# System_Regulators.net
KiCad netlist of a schematic drawn in Altium Designer
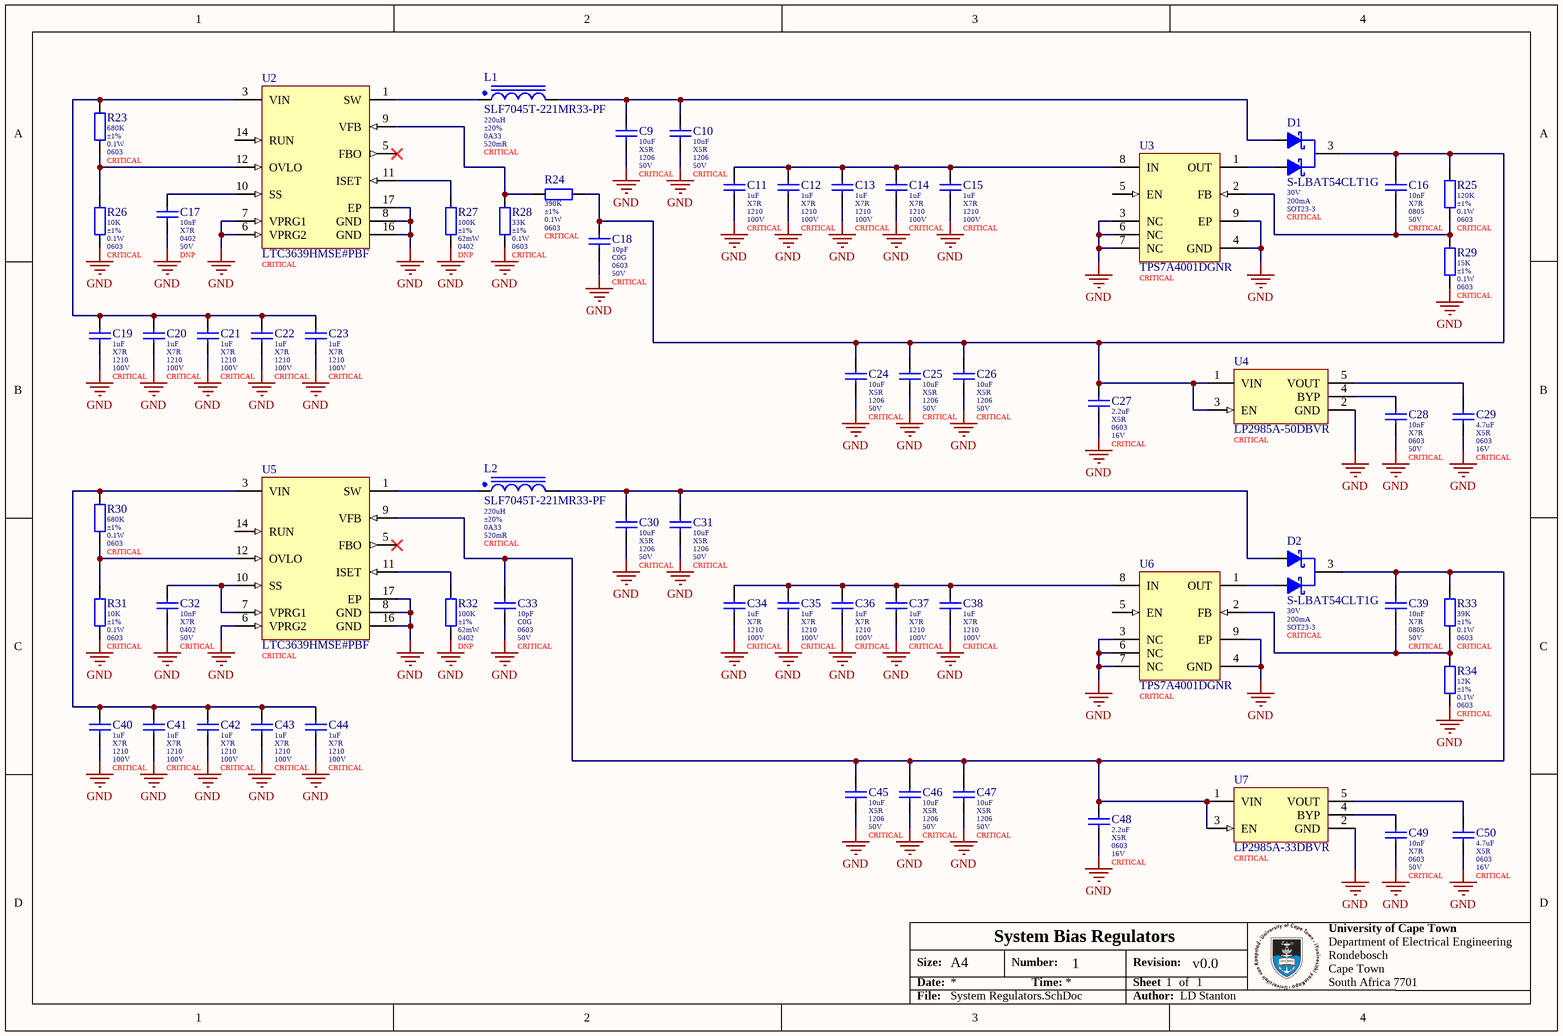
[diagram p0: System Regulators.SchDoc]

(export (version "E")
  (design (tool "Eeschema 10.0.6"))
  (components
    (comp (ref "C9")
      (value "10uF")
      (footprint "1206_160_H_N")
      (description "MLCC 10uF 1206 50V X5R ±10%")
      (fields
        (field (name "DIELECTRIC") "X5R")
        (field (name "PACKAGE") "1206")
        (field (name "VOLTAGE") "50V")
        (field (name "POPULATE") "CRITICAL")
        (field (name "LCSC PART NUMBER") "C13585")
        (field (name "MANUFACTURER") "Samsung")
      )
      (libsource (lib "University of Cape Town") (part "Symbol"))
    )
    (comp (ref "C10")
      (value "10uF")
      (footprint "1206_160_H_N")
      (description "MLCC 10uF 1206 50V X5R ±10%")
      (fields
        (field (name "DIELECTRIC") "X5R")
        (field (name "PACKAGE") "1206")
        (field (name "VOLTAGE") "50V")
        (field (name "POPULATE") "CRITICAL")
        (field (name "LCSC PART NUMBER") "C13585")
        (field (name "MANUFACTURER") "Samsung")
      )
      (libsource (lib "University of Cape Town") (part "Symbol"))
    )
    (comp (ref "C11")
      (value "1uF")
      (footprint "1210_250_J_N")
      (description "MLCC 1uF 1210 100V X7R ±10%")
      (fields
        (field (name "DIELECTRIC") "X7R")
        (field (name "PACKAGE") "1210")
        (field (name "VOLTAGE") "100V")
        (field (name "POPULATE") "CRITICAL")
        (field (name "LCSC PART NUMBER") "C444847")
        (field (name "TOLERANCE") "±10%")
      )
      (libsource (lib "University of Cape Town") (part "Symbol"))
    )
    (comp (ref "C12")
      (value "1uF")
      (footprint "1210_250_J_N")
      (description "MLCC 1uF 1210 100V X7R ±10%")
      (fields
        (field (name "DIELECTRIC") "X7R")
        (field (name "PACKAGE") "1210")
        (field (name "VOLTAGE") "100V")
        (field (name "POPULATE") "CRITICAL")
        (field (name "LCSC PART NUMBER") "C444847")
        (field (name "TOLERANCE") "±10%")
      )
      (libsource (lib "University of Cape Town") (part "Symbol"))
    )
    (comp (ref "C13")
      (value "1uF")
      (footprint "1210_250_J_N")
      (description "MLCC 1uF 1210 100V X7R ±10%")
      (fields
        (field (name "DIELECTRIC") "X7R")
        (field (name "PACKAGE") "1210")
        (field (name "VOLTAGE") "100V")
        (field (name "POPULATE") "CRITICAL")
        (field (name "LCSC PART NUMBER") "C444847")
        (field (name "TOLERANCE") "±10%")
      )
      (libsource (lib "University of Cape Town") (part "Symbol"))
    )
    (comp (ref "C14")
      (value "1uF")
      (footprint "1210_250_J_N")
      (description "MLCC 1uF 1210 100V X7R ±10%")
      (fields
        (field (name "DIELECTRIC") "X7R")
        (field (name "PACKAGE") "1210")
        (field (name "VOLTAGE") "100V")
        (field (name "POPULATE") "CRITICAL")
        (field (name "LCSC PART NUMBER") "C444847")
        (field (name "TOLERANCE") "±10%")
      )
      (libsource (lib "University of Cape Town") (part "Symbol"))
    )
    (comp (ref "C15")
      (value "1uF")
      (footprint "1210_250_J_N")
      (description "MLCC 1uF 1210 100V X7R ±10%")
      (fields
        (field (name "DIELECTRIC") "X7R")
        (field (name "PACKAGE") "1210")
        (field (name "VOLTAGE") "100V")
        (field (name "POPULATE") "CRITICAL")
        (field (name "LCSC PART NUMBER") "C444847")
        (field (name "TOLERANCE") "±10%")
      )
      (libsource (lib "University of Cape Town") (part "Symbol"))
    )
    (comp (ref "C16")
      (value "10nF")
      (footprint "0605_065_A_N")
      (description "MLCC 10nF 0805 50V X7R ±10%")
      (fields
        (field (name "DIELECTRIC") "X7R")
        (field (name "PACKAGE") "0805")
        (field (name "VOLTAGE") "50V")
        (field (name "POPULATE") "CRITICAL")
        (field (name "LCSC PART NUMBER") "C1710")
        (field (name "MANUFACTURER") "Samsung")
      )
      (libsource (lib "University of Cape Town") (part "Symbol"))
    )
    (comp (ref "C17")
      (value "10nF")
      (footprint "0402_050_5_N")
      (description "MLCC 10nF 0402 50V X7R ±10%")
      (fields
        (field (name "DIELECTRIC") "X7R")
        (field (name "PACKAGE") "0402")
        (field (name "VOLTAGE") "50V")
        (field (name "POPULATE") "DNP")
        (field (name "TOLERANCE") "±10%")
        (field (name "LCSC PART NUMBER") "C15195")
      )
      (libsource (lib "University of Cape Town") (part "Symbol"))
    )
    (comp (ref "C18")
      (value "10pF")
      (footprint "0603_080_8_N")
      (description "MLCC 10pF 0603 C0G ±0.1pF")
      (fields
        (field (name "DIELECTRIC") "C0G")
        (field (name "PACKAGE") "0603")
        (field (name "VOLTAGE") "50V")
        (field (name "POPULATE") "CRITICAL")
        (field (name "LCSC PART NUMBER") "C1634")
        (field (name "MANUFACTURER") "Samsung")
      )
      (libsource (lib "University of Cape Town") (part "Symbol"))
    )
    (comp (ref "C19")
      (value "1uF")
      (footprint "1210_250_J_N")
      (description "MLCC 1uF 1210 100V X7R ±10%")
      (fields
        (field (name "DIELECTRIC") "X7R")
        (field (name "PACKAGE") "1210")
        (field (name "VOLTAGE") "100V")
        (field (name "POPULATE") "CRITICAL")
        (field (name "LCSC PART NUMBER") "C444847")
        (field (name "TOLERANCE") "±10%")
      )
      (libsource (lib "University of Cape Town") (part "Symbol"))
    )
    (comp (ref "C20")
      (value "1uF")
      (footprint "1210_250_J_N")
      (description "MLCC 1uF 1210 100V X7R ±10%")
      (fields
        (field (name "DIELECTRIC") "X7R")
        (field (name "PACKAGE") "1210")
        (field (name "VOLTAGE") "100V")
        (field (name "POPULATE") "CRITICAL")
        (field (name "LCSC PART NUMBER") "C444847")
        (field (name "TOLERANCE") "±10%")
      )
      (libsource (lib "University of Cape Town") (part "Symbol"))
    )
    (comp (ref "C21")
      (value "1uF")
      (footprint "1210_250_J_N")
      (description "MLCC 1uF 1210 100V X7R ±10%")
      (fields
        (field (name "DIELECTRIC") "X7R")
        (field (name "PACKAGE") "1210")
        (field (name "VOLTAGE") "100V")
        (field (name "POPULATE") "CRITICAL")
        (field (name "LCSC PART NUMBER") "C444847")
        (field (name "TOLERANCE") "±10%")
      )
      (libsource (lib "University of Cape Town") (part "Symbol"))
    )
    (comp (ref "C22")
      (value "1uF")
      (footprint "1210_250_J_N")
      (description "MLCC 1uF 1210 100V X7R ±10%")
      (fields
        (field (name "DIELECTRIC") "X7R")
        (field (name "PACKAGE") "1210")
        (field (name "VOLTAGE") "100V")
        (field (name "POPULATE") "CRITICAL")
        (field (name "LCSC PART NUMBER") "C444847")
        (field (name "TOLERANCE") "±10%")
      )
      (libsource (lib "University of Cape Town") (part "Symbol"))
    )
    (comp (ref "C23")
      (value "1uF")
      (footprint "1210_250_J_N")
      (description "MLCC 1uF 1210 100V X7R ±10%")
      (fields
        (field (name "DIELECTRIC") "X7R")
        (field (name "PACKAGE") "1210")
        (field (name "VOLTAGE") "100V")
        (field (name "POPULATE") "CRITICAL")
        (field (name "LCSC PART NUMBER") "C444847")
        (field (name "TOLERANCE") "±10%")
      )
      (libsource (lib "University of Cape Town") (part "Symbol"))
    )
    (comp (ref "C24")
      (value "10uF")
      (footprint "1206_160_H_N")
      (description "MLCC 10uF 1206 50V X5R ±10%")
      (fields
        (field (name "DIELECTRIC") "X5R")
        (field (name "PACKAGE") "1206")
        (field (name "VOLTAGE") "50V")
        (field (name "POPULATE") "CRITICAL")
        (field (name "LCSC PART NUMBER") "C13585")
        (field (name "MANUFACTURER") "Samsung")
      )
      (libsource (lib "University of Cape Town") (part "Symbol"))
    )
    (comp (ref "C25")
      (value "10uF")
      (footprint "1206_160_H_N")
      (description "MLCC 10uF 1206 50V X5R ±10%")
      (fields
        (field (name "DIELECTRIC") "X5R")
        (field (name "PACKAGE") "1206")
        (field (name "VOLTAGE") "50V")
        (field (name "POPULATE") "CRITICAL")
        (field (name "LCSC PART NUMBER") "C13585")
        (field (name "MANUFACTURER") "Samsung")
      )
      (libsource (lib "University of Cape Town") (part "Symbol"))
    )
    (comp (ref "C26")
      (value "10uF")
      (footprint "1206_160_H_N")
      (description "MLCC 10uF 1206 50V X5R ±10%")
      (fields
        (field (name "DIELECTRIC") "X5R")
        (field (name "PACKAGE") "1206")
        (field (name "VOLTAGE") "50V")
        (field (name "POPULATE") "CRITICAL")
        (field (name "LCSC PART NUMBER") "C13585")
        (field (name "MANUFACTURER") "Samsung")
      )
      (libsource (lib "University of Cape Town") (part "Symbol"))
    )
    (comp (ref "C27")
      (value "2.2uF")
      (footprint "0603_080_8_N")
      (description "MLCC 2.2uF 0603 16V X5R ±10%")
      (fields
        (field (name "DIELECTRIC") "X5R")
        (field (name "PACKAGE") "0603")
        (field (name "VOLTAGE") "16V")
        (field (name "POPULATE") "CRITICAL")
        (field (name "TOLERANCE") "±10%")
        (field (name "LCSC PART NUMBER") "C23630")
      )
      (libsource (lib "University of Cape Town") (part "Symbol"))
    )
    (comp (ref "C28")
      (value "10nF")
      (footprint "0603_080")
      (description "MLCC 10nF 0603 50V X7R ±10%")
      (fields
        (field (name "DIELECTRIC") "X7R")
        (field (name "PACKAGE") "0603")
        (field (name "VOLTAGE") "50V")
        (field (name "POPULATE") "CRITICAL")
        (field (name "LCSC PART NUMBER") "C57112")
        (field (name "MANUFACTURER") "Guandong")
      )
      (libsource (lib "University of Cape Town") (part "Symbol"))
    )
    (comp (ref "C29")
      (value "4.7uF")
      (footprint "0603_080_8_N")
      (description "MLCC 4.7uF 0603 16V X5R ±10%")
      (fields
        (field (name "DIELECTRIC") "X5R")
        (field (name "PACKAGE") "0603")
        (field (name "VOLTAGE") "16V")
        (field (name "POPULATE") "CRITICAL")
        (field (name "LCSC PART NUMBER") "C19666")
        (field (name "TOLERANCE") "±10%")
      )
      (libsource (lib "University of Cape Town") (part "Symbol"))
    )
    (comp (ref "C30")
      (value "10uF")
      (footprint "1206_160_H_N")
      (description "MLCC 10uF 1206 50V X5R ±10%")
      (fields
        (field (name "DIELECTRIC") "X5R")
        (field (name "PACKAGE") "1206")
        (field (name "VOLTAGE") "50V")
        (field (name "POPULATE") "CRITICAL")
        (field (name "LCSC PART NUMBER") "C13585")
        (field (name "MANUFACTURER") "Samsung")
      )
      (libsource (lib "University of Cape Town") (part "Symbol"))
    )
    (comp (ref "C31")
      (value "10uF")
      (footprint "1206_160_H_N")
      (description "MLCC 10uF 1206 50V X5R ±10%")
      (fields
        (field (name "DIELECTRIC") "X5R")
        (field (name "PACKAGE") "1206")
        (field (name "VOLTAGE") "50V")
        (field (name "POPULATE") "CRITICAL")
        (field (name "LCSC PART NUMBER") "C13585")
        (field (name "MANUFACTURER") "Samsung")
      )
      (libsource (lib "University of Cape Town") (part "Symbol"))
    )
    (comp (ref "C32")
      (value "10nF")
      (footprint "0402_050_5_N")
      (description "MLCC 10nF 0402 50V X7R ±10%")
      (fields
        (field (name "DIELECTRIC") "X7R")
        (field (name "PACKAGE") "0402")
        (field (name "VOLTAGE") "50V")
        (field (name "POPULATE") "CRITICAL")
        (field (name "TOLERANCE") "±10%")
        (field (name "LCSC PART NUMBER") "C15195")
      )
      (libsource (lib "University of Cape Town") (part "Symbol"))
    )
    (comp (ref "C33")
      (value "10pF")
      (footprint "0603_080_8_N")
      (description "MLCC 10pF 0603 C0G ±0.1pF")
      (fields
        (field (name "DIELECTRIC") "C0G")
        (field (name "PACKAGE") "0603")
        (field (name "VOLTAGE") "50V")
        (field (name "POPULATE") "CRITICAL")
        (field (name "LCSC PART NUMBER") "C1634")
        (field (name "MANUFACTURER") "Samsung")
      )
      (libsource (lib "University of Cape Town") (part "Symbol"))
    )
    (comp (ref "C34")
      (value "1uF")
      (footprint "1210_250_J_N")
      (description "MLCC 1uF 1210 100V X7R ±10%")
      (fields
        (field (name "DIELECTRIC") "X7R")
        (field (name "PACKAGE") "1210")
        (field (name "VOLTAGE") "100V")
        (field (name "POPULATE") "CRITICAL")
        (field (name "LCSC PART NUMBER") "C444847")
        (field (name "TOLERANCE") "±10%")
      )
      (libsource (lib "University of Cape Town") (part "Symbol"))
    )
    (comp (ref "C35")
      (value "1uF")
      (footprint "1210_250_J_N")
      (description "MLCC 1uF 1210 100V X7R ±10%")
      (fields
        (field (name "DIELECTRIC") "X7R")
        (field (name "PACKAGE") "1210")
        (field (name "VOLTAGE") "100V")
        (field (name "POPULATE") "CRITICAL")
        (field (name "LCSC PART NUMBER") "C444847")
        (field (name "TOLERANCE") "±10%")
      )
      (libsource (lib "University of Cape Town") (part "Symbol"))
    )
    (comp (ref "C36")
      (value "1uF")
      (footprint "1210_250_J_N")
      (description "MLCC 1uF 1210 100V X7R ±10%")
      (fields
        (field (name "DIELECTRIC") "X7R")
        (field (name "PACKAGE") "1210")
        (field (name "VOLTAGE") "100V")
        (field (name "POPULATE") "CRITICAL")
        (field (name "LCSC PART NUMBER") "C444847")
        (field (name "TOLERANCE") "±10%")
      )
      (libsource (lib "University of Cape Town") (part "Symbol"))
    )
    (comp (ref "C37")
      (value "1uF")
      (footprint "1210_250_J_N")
      (description "MLCC 1uF 1210 100V X7R ±10%")
      (fields
        (field (name "DIELECTRIC") "X7R")
        (field (name "PACKAGE") "1210")
        (field (name "VOLTAGE") "100V")
        (field (name "POPULATE") "CRITICAL")
        (field (name "LCSC PART NUMBER") "C444847")
        (field (name "TOLERANCE") "±10%")
      )
      (libsource (lib "University of Cape Town") (part "Symbol"))
    )
    (comp (ref "C38")
      (value "1uF")
      (footprint "1210_250_J_N")
      (description "MLCC 1uF 1210 100V X7R ±10%")
      (fields
        (field (name "DIELECTRIC") "X7R")
        (field (name "PACKAGE") "1210")
        (field (name "VOLTAGE") "100V")
        (field (name "POPULATE") "CRITICAL")
        (field (name "LCSC PART NUMBER") "C444847")
        (field (name "TOLERANCE") "±10%")
      )
      (libsource (lib "University of Cape Town") (part "Symbol"))
    )
    (comp (ref "C39")
      (value "10nF")
      (footprint "0605_065_A_N")
      (description "MLCC 10nF 0805 50V X7R ±10%")
      (fields
        (field (name "DIELECTRIC") "X7R")
        (field (name "PACKAGE") "0805")
        (field (name "VOLTAGE") "50V")
        (field (name "POPULATE") "CRITICAL")
        (field (name "LCSC PART NUMBER") "C1710")
        (field (name "MANUFACTURER") "Samsung")
      )
      (libsource (lib "University of Cape Town") (part "Symbol"))
    )
    (comp (ref "C40")
      (value "1uF")
      (footprint "1210_250_J_N")
      (description "MLCC 1uF 1210 100V X7R ±10%")
      (fields
        (field (name "DIELECTRIC") "X7R")
        (field (name "PACKAGE") "1210")
        (field (name "VOLTAGE") "100V")
        (field (name "POPULATE") "CRITICAL")
        (field (name "LCSC PART NUMBER") "C444847")
        (field (name "TOLERANCE") "±10%")
      )
      (libsource (lib "University of Cape Town") (part "Symbol"))
    )
    (comp (ref "C41")
      (value "1uF")
      (footprint "1210_250_J_N")
      (description "MLCC 1uF 1210 100V X7R ±10%")
      (fields
        (field (name "DIELECTRIC") "X7R")
        (field (name "PACKAGE") "1210")
        (field (name "VOLTAGE") "100V")
        (field (name "POPULATE") "CRITICAL")
        (field (name "LCSC PART NUMBER") "C444847")
        (field (name "TOLERANCE") "±10%")
      )
      (libsource (lib "University of Cape Town") (part "Symbol"))
    )
    (comp (ref "C42")
      (value "1uF")
      (footprint "1210_250_J_N")
      (description "MLCC 1uF 1210 100V X7R ±10%")
      (fields
        (field (name "DIELECTRIC") "X7R")
        (field (name "PACKAGE") "1210")
        (field (name "VOLTAGE") "100V")
        (field (name "POPULATE") "CRITICAL")
        (field (name "LCSC PART NUMBER") "C444847")
        (field (name "TOLERANCE") "±10%")
      )
      (libsource (lib "University of Cape Town") (part "Symbol"))
    )
    (comp (ref "C43")
      (value "1uF")
      (footprint "1210_250_J_N")
      (description "MLCC 1uF 1210 100V X7R ±10%")
      (fields
        (field (name "DIELECTRIC") "X7R")
        (field (name "PACKAGE") "1210")
        (field (name "VOLTAGE") "100V")
        (field (name "POPULATE") "CRITICAL")
        (field (name "LCSC PART NUMBER") "C444847")
        (field (name "TOLERANCE") "±10%")
      )
      (libsource (lib "University of Cape Town") (part "Symbol"))
    )
    (comp (ref "C44")
      (value "1uF")
      (footprint "1210_250_J_N")
      (description "MLCC 1uF 1210 100V X7R ±10%")
      (fields
        (field (name "DIELECTRIC") "X7R")
        (field (name "PACKAGE") "1210")
        (field (name "VOLTAGE") "100V")
        (field (name "POPULATE") "CRITICAL")
        (field (name "LCSC PART NUMBER") "C444847")
        (field (name "TOLERANCE") "±10%")
      )
      (libsource (lib "University of Cape Town") (part "Symbol"))
    )
    (comp (ref "C45")
      (value "10uF")
      (footprint "1206_160_H_N")
      (description "MLCC 10uF 1206 50V X5R ±10%")
      (fields
        (field (name "DIELECTRIC") "X5R")
        (field (name "PACKAGE") "1206")
        (field (name "VOLTAGE") "50V")
        (field (name "POPULATE") "CRITICAL")
        (field (name "LCSC PART NUMBER") "C13585")
        (field (name "MANUFACTURER") "Samsung")
      )
      (libsource (lib "University of Cape Town") (part "Symbol"))
    )
    (comp (ref "C46")
      (value "10uF")
      (footprint "1206_160_H_N")
      (description "MLCC 10uF 1206 50V X5R ±10%")
      (fields
        (field (name "DIELECTRIC") "X5R")
        (field (name "PACKAGE") "1206")
        (field (name "VOLTAGE") "50V")
        (field (name "POPULATE") "CRITICAL")
        (field (name "LCSC PART NUMBER") "C13585")
        (field (name "MANUFACTURER") "Samsung")
      )
      (libsource (lib "University of Cape Town") (part "Symbol"))
    )
    (comp (ref "C47")
      (value "10uF")
      (footprint "1206_160_H_N")
      (description "MLCC 10uF 1206 50V X5R ±10%")
      (fields
        (field (name "DIELECTRIC") "X5R")
        (field (name "PACKAGE") "1206")
        (field (name "VOLTAGE") "50V")
        (field (name "POPULATE") "CRITICAL")
        (field (name "LCSC PART NUMBER") "C13585")
        (field (name "MANUFACTURER") "Samsung")
      )
      (libsource (lib "University of Cape Town") (part "Symbol"))
    )
    (comp (ref "C48")
      (value "2.2uF")
      (footprint "0603_080_8_N")
      (description "MLCC 2.2uF 0603 16V X5R ±10%")
      (fields
        (field (name "DIELECTRIC") "X5R")
        (field (name "PACKAGE") "0603")
        (field (name "VOLTAGE") "16V")
        (field (name "POPULATE") "CRITICAL")
        (field (name "TOLERANCE") "±10%")
        (field (name "LCSC PART NUMBER") "C23630")
      )
      (libsource (lib "University of Cape Town") (part "Symbol"))
    )
    (comp (ref "C49")
      (value "10nF")
      (footprint "0603_080")
      (description "MLCC 10nF 0603 50V X7R ±10%")
      (fields
        (field (name "DIELECTRIC") "X7R")
        (field (name "PACKAGE") "0603")
        (field (name "VOLTAGE") "50V")
        (field (name "POPULATE") "CRITICAL")
        (field (name "LCSC PART NUMBER") "C57112")
        (field (name "MANUFACTURER") "Guandong")
      )
      (libsource (lib "University of Cape Town") (part "Symbol"))
    )
    (comp (ref "C50")
      (value "4.7uF")
      (footprint "0603_080_8_N")
      (description "MLCC 4.7uF 0603 16V X5R ±10%")
      (fields
        (field (name "DIELECTRIC") "X5R")
        (field (name "PACKAGE") "0603")
        (field (name "VOLTAGE") "16V")
        (field (name "POPULATE") "CRITICAL")
        (field (name "LCSC PART NUMBER") "C19666")
        (field (name "TOLERANCE") "±10%")
      )
      (libsource (lib "University of Cape Town") (part "Symbol"))
    )
    (comp (ref "D1")
      (value "S-LBAT54CLT1G")
      (footprint "SOT-23-3 (LBAT54C) B")
      (description "Schottky Barrier Diode Common Cathode 30V 200mA")
      (fields
        (field (name "REVERSE VOLTAGE") "30V")
        (field (name "FORWARD CURRENT") "200mA")
        (field (name "PACKAGE") "SOT23-3")
        (field (name "PLACEMENT") "CRITICAL")
        (field (name "MANUFACTURER") "LRC")
        (field (name "LCSC PART NUMBER") "C559091")
      )
      (libsource (lib "University of Cape Town") (part "BAT54"))
    )
    (comp (ref "D2")
      (value "S-LBAT54CLT1G")
      (footprint "SOT-23-3 (LBAT54C) B")
      (description "Schottky Barrier Diode Common Cathode 30V 200mA")
      (fields
        (field (name "REVERSE VOLTAGE") "30V")
        (field (name "FORWARD CURRENT") "200mA")
        (field (name "PACKAGE") "SOT23-3")
        (field (name "PLACEMENT") "CRITICAL")
        (field (name "MANUFACTURER") "LRC")
        (field (name "LCSC PART NUMBER") "C559091")
      )
      (libsource (lib "University of Cape Town") (part "BAT54"))
    )
    (comp (ref "L1")
      (value "SLF7045T-221MR33-PF")
      (footprint "SLF7045 B")
      (description "Inductor 220uH ±20% 0A65 470mR Wirewound Shielded")
      (fields
        (field (name "ALTIUM_VALUE") "220uH")
        (field (name "TOLERANCE") "±20%")
        (field (name "RATED CURRENT") "0A33")
        (field (name "DC RESISTANCE") "520mR")
        (field (name "POPULATE") "CRITICAL")
        (field (name "MANUFACTURER") "TDK")
        (field (name "LCSC PART NUMBER") "C24679")
      )
      (libsource (lib "University of Cape Town") (part "Inductor Core Polarised"))
    )
    (comp (ref "L2")
      (value "SLF7045T-221MR33-PF")
      (footprint "SLF7045 B")
      (description "Inductor 220uH ±20% 0A65 470mR Wirewound Shielded")
      (fields
        (field (name "ALTIUM_VALUE") "220uH")
        (field (name "TOLERANCE") "±20%")
        (field (name "RATED CURRENT") "0A33")
        (field (name "DC RESISTANCE") "520mR")
        (field (name "POPULATE") "CRITICAL")
        (field (name "MANUFACTURER") "TDK")
        (field (name "LCSC PART NUMBER") "C24679")
      )
      (libsource (lib "University of Cape Town") (part "Inductor Core Polarised"))
    )
    (comp (ref "R23")
      (value "680K")
      (footprint "0603")
      (description "Resistor 680K 0603 ±1% Thick Film Uniroyal")
      (fields
        (field (name "TOLERANCE") "±1%")
        (field (name "POWER") "0.1W")
        (field (name "PACKAGE") "0603")
        (field (name "POPULATE") "CRITICAL")
        (field (name "LCSC PART NUMBER") "C25822")
        (field (name "MANUFACTURER") "Uniroyal")
      )
      (libsource (lib "University of Cape Town") (part "Chip Resistor"))
    )
    (comp (ref "R24")
      (value "390K")
      (footprint "0603")
      (description "Resistor 390K 0603 ±1%Thick Film Uniroyal Elec")
      (fields
        (field (name "TOLERANCE") "±1%")
        (field (name "POWER") "0.1W")
        (field (name "PACKAGE") "0603")
        (field (name "POPULATE") "CRITICAL")
        (field (name "LCSC PART NUMBER") "C23150")
        (field (name "Comment") "0603WAF3903T5E")
      )
      (libsource (lib "University of Cape Town") (part "Chip Resistor"))
    )
    (comp (ref "R25")
      (value "120K")
      (footprint "0603")
      (description "Resistor 120K 0603 ±1% Thick Film Uniroyal")
      (fields
        (field (name "TOLERANCE") "±1%")
        (field (name "POWER") "0.1W")
        (field (name "PACKAGE") "0603")
        (field (name "POPULATE") "CRITICAL")
        (field (name "MANUFACTURER") "Uniroyal")
        (field (name "LCSC PART NUMBER") "C25808")
      )
      (libsource (lib "University of Cape Town") (part "Chip Resistor"))
    )
    (comp (ref "R26")
      (value "10K")
      (footprint "0603")
      (description "Resistor 10K 0603 ±1% Thick Film Uniroyal")
      (fields
        (field (name "TOLERANCE") "±1%")
        (field (name "POWER") "0.1W")
        (field (name "PACKAGE") "0603")
        (field (name "POPULATE") "CRITICAL")
        (field (name "MANUFACTURER") "Uniroyal")
        (field (name "LCSC PART NUMBER") "C25804")
      )
      (libsource (lib "University of Cape Town") (part "Chip Resistor"))
    )
    (comp (ref "R27")
      (value "100K")
      (footprint "0402")
      (description "Resistor 100K 0402 ±1% Thick Film Uniroyal")
      (fields
        (field (name "TOLERANCE") "±1%")
        (field (name "POWER") "62mW")
        (field (name "PACKAGE") "0402")
        (field (name "POPULATE") "DNP")
        (field (name "LCSC PART NUMBER") "C25741")
        (field (name "MANUFACTURER") "Uniroyal")
      )
      (libsource (lib "University of Cape Town") (part "Chip Resistor"))
    )
    (comp (ref "R28")
      (value "33K")
      (footprint "0603")
      (description "Resistor 33K 0603 ±1% Thick Film Uniroyal")
      (fields
        (field (name "TOLERANCE") "±1%")
        (field (name "POWER") "0.1W")
        (field (name "PACKAGE") "0603")
        (field (name "POPULATE") "CRITICAL")
        (field (name "LCSC PART NUMBER") "C4216")
        (field (name "MANUFACTURER") "Uniroyal")
      )
      (libsource (lib "University of Cape Town") (part "Chip Resistor"))
    )
    (comp (ref "R29")
      (value "15K")
      (footprint "0603")
      (description "Resistor 15K 0603 ±1% Thick Film Uniroyal")
      (fields
        (field (name "TOLERANCE") "±1%")
        (field (name "POWER") "0.1W")
        (field (name "PACKAGE") "0603")
        (field (name "POPULATE") "CRITICAL")
        (field (name "MANUFACTURER") "Uniroyal")
        (field (name "LCSC PART NUMBER") "C22809")
      )
      (libsource (lib "University of Cape Town") (part "Chip Resistor"))
    )
    (comp (ref "R30")
      (value "680K")
      (footprint "0603")
      (description "Resistor 680K 0603 ±1% Thick Film Uniroyal")
      (fields
        (field (name "TOLERANCE") "±1%")
        (field (name "POWER") "0.1W")
        (field (name "PACKAGE") "0603")
        (field (name "POPULATE") "CRITICAL")
        (field (name "LCSC PART NUMBER") "C25822")
        (field (name "MANUFACTURER") "Uniroyal")
      )
      (libsource (lib "University of Cape Town") (part "Chip Resistor"))
    )
    (comp (ref "R31")
      (value "10K")
      (footprint "0603")
      (description "Resistor 10K 0603 ±1% Thick Film Uniroyal")
      (fields
        (field (name "TOLERANCE") "±1%")
        (field (name "POWER") "0.1W")
        (field (name "PACKAGE") "0603")
        (field (name "POPULATE") "CRITICAL")
        (field (name "MANUFACTURER") "Uniroyal")
        (field (name "LCSC PART NUMBER") "C25804")
      )
      (libsource (lib "University of Cape Town") (part "Chip Resistor"))
    )
    (comp (ref "R32")
      (value "100K")
      (footprint "0402")
      (description "Resistor 100K 0402 ±1% Thick Film Uniroyal")
      (fields
        (field (name "TOLERANCE") "±1%")
        (field (name "POWER") "62mW")
        (field (name "PACKAGE") "0402")
        (field (name "POPULATE") "DNP")
        (field (name "LCSC PART NUMBER") "C25741")
        (field (name "MANUFACTURER") "Uniroyal")
      )
      (libsource (lib "University of Cape Town") (part "Chip Resistor"))
    )
    (comp (ref "R33")
      (value "39K")
      (footprint "0603")
      (description "Resistor 39K 0603 ±1% Thick Film Uniroyal")
      (fields
        (field (name "TOLERANCE") "±1%")
        (field (name "POWER") "0.1W")
        (field (name "PACKAGE") "0603")
        (field (name "POPULATE") "CRITICAL")
        (field (name "MANUFACTURER") "Uniroyal")
        (field (name "Comment") "0603WAF3902T5E")
      )
      (libsource (lib "University of Cape Town") (part "Chip Resistor"))
    )
    (comp (ref "R34")
      (value "12K")
      (footprint "0603")
      (description "Resistor 12K 0603 ±1% Thick Film Uniroyal")
      (fields
        (field (name "TOLERANCE") "±1%")
        (field (name "POWER") "0.1W")
        (field (name "PACKAGE") "0603")
        (field (name "POPULATE") "CRITICAL")
        (field (name "MANUFACTURER") "Uniroyal")
        (field (name "LCSC PART NUMBER") "C22790")
      )
      (libsource (lib "University of Cape Town") (part "Chip Resistor"))
    )
    (comp (ref "U2")
      (value "LTC3639HMSE#PBF")
      (footprint "LT-MSE-16-V(12)4PR-EDP_N")
      (description "DC-DC Conv 4V to 150V Synchronous Step Down Single-Out 0.8V to 150V 0.1A Automotive 12-Pin MSOP EP")
      (fields (field (name "PLACEMENT") "CRITICAL") (field (name "LCSC PART NUMBER") "C117279"))
      (libsource (lib "University of Cape Town") (part "LT-LTC3639-MSE-16"))
    )
    (comp (ref "U3")
      (value "TPS7A4001DGNR")
      (footprint "DGN0008B_N")
      (description "Adjustable LDO Voltage Regulator, 7 V to 100 V, 780 mV Drop, 1.161 V to 90 V / 50 mA out, MSOP-8")
      (fields
        (field (name "PLACEMENT") "CRITICAL")
        (field (name "LCSC PART NUMBER") "C55006")
        (field (name "POWER") "1.83W")
      )
      (libsource (lib "University of Cape Town") (part "TPS7A4001DGNR"))
    )
    (comp (ref "U4")
      (value "LP2985A-50DBVR")
      (footprint "SOT-23-5 (DBV0005A) B")
      (description "LDO Fixed 5V, 0.15A, 1% Accuracy, Max 16V Input, 65uA Iq, SOT-23-5")
      (fields
        (field (name "PLACEMENT") "CRITICAL")
        (field (name "LCSC PART NUMBER") "C109382")
        (field (name "MANUFACTURER") "Texas Instruments")
      )
      (libsource (lib "University of Cape Town") (part "LP2985"))
    )
    (comp (ref "U5")
      (value "LTC3639HMSE#PBF")
      (footprint "LT-MSE-16-V(12)4PR-EDP_N")
      (description "DC-DC Conv 4V to 150V Synchronous Step Down Single-Out 0.8V to 150V 0.1A Automotive 12-Pin MSOP EP")
      (fields (field (name "PLACEMENT") "CRITICAL") (field (name "LCSC PART NUMBER") "C117279"))
      (libsource (lib "University of Cape Town") (part "LT-LTC3639-MSE-16"))
    )
    (comp (ref "U6")
      (value "TPS7A4001DGNR")
      (footprint "DGN0008B_N")
      (description "Adjustable LDO Voltage Regulator, 7 V to 100 V, 780 mV Drop, 1.161 V to 90 V / 50 mA out, MSOP-8")
      (fields
        (field (name "PLACEMENT") "CRITICAL")
        (field (name "LCSC PART NUMBER") "C55006")
        (field (name "POWER") "1.83W")
      )
      (libsource (lib "University of Cape Town") (part "TPS7A4001DGNR"))
    )
    (comp (ref "U7")
      (value "LP2985A-33DBVR")
      (footprint "SOT-23-5 (DBV0005A) B")
      (description "LDO Fixed 3V3, 0.15A, 1% Accuracy, Max 16V Input, 65uA Iq, SOT-23-5")
      (fields
        (field (name "PLACEMENT") "CRITICAL")
        (field (name "MANUFACTURER") "Texas Instruments")
        (field (name "LCSC PART NUMBER") "C89826")
      )
      (libsource (lib "University of Cape Town") (part "LP2985"))
    )
  )
  (nets
    (net (code "1") (name "GND") (class "Default")
      (node (ref "C10") (pin "2") (pinfunction "2_2") (pintype "passive"))
      (node (ref "C11") (pin "2") (pinfunction "2_2") (pintype "passive"))
      (node (ref "C12") (pin "2") (pinfunction "2_2") (pintype "passive"))
      (node (ref "C13") (pin "2") (pinfunction "2_2") (pintype "passive"))
      (node (ref "C14") (pin "2") (pinfunction "2_2") (pintype "passive"))
      (node (ref "C15") (pin "2") (pinfunction "2_2") (pintype "passive"))
      (node (ref "C17") (pin "2") (pinfunction "2_2") (pintype "passive"))
      (node (ref "C18") (pin "2") (pinfunction "2_2") (pintype "passive"))
      (node (ref "C19") (pin "2") (pinfunction "2_2") (pintype "passive"))
      (node (ref "C20") (pin "2") (pinfunction "2_2") (pintype "passive"))
      (node (ref "C21") (pin "2") (pinfunction "2_2") (pintype "passive"))
      (node (ref "C22") (pin "2") (pinfunction "2_2") (pintype "passive"))
      (node (ref "C23") (pin "2") (pinfunction "2_2") (pintype "passive"))
      (node (ref "C24") (pin "2") (pinfunction "2_2") (pintype "passive"))
      (node (ref "C25") (pin "2") (pinfunction "2_2") (pintype "passive"))
      (node (ref "C26") (pin "2") (pinfunction "2_2") (pintype "passive"))
      (node (ref "C27") (pin "2") (pinfunction "2_2") (pintype "passive"))
      (node (ref "C28") (pin "2") (pinfunction "2_2") (pintype "passive"))
      (node (ref "C29") (pin "2") (pinfunction "2_2") (pintype "passive"))
      (node (ref "C30") (pin "2") (pinfunction "2_2") (pintype "passive"))
      (node (ref "C31") (pin "2") (pinfunction "2_2") (pintype "passive"))
      (node (ref "C32") (pin "2") (pinfunction "2_2") (pintype "passive"))
      (node (ref "C33") (pin "2") (pinfunction "2_2") (pintype "passive"))
      (node (ref "C34") (pin "2") (pinfunction "2_2") (pintype "passive"))
      (node (ref "C35") (pin "2") (pinfunction "2_2") (pintype "passive"))
      (node (ref "C36") (pin "2") (pinfunction "2_2") (pintype "passive"))
      (node (ref "C37") (pin "2") (pinfunction "2_2") (pintype "passive"))
      (node (ref "C38") (pin "2") (pinfunction "2_2") (pintype "passive"))
      (node (ref "C40") (pin "2") (pinfunction "2_2") (pintype "passive"))
      (node (ref "C41") (pin "2") (pinfunction "2_2") (pintype "passive"))
      (node (ref "C42") (pin "2") (pinfunction "2_2") (pintype "passive"))
      (node (ref "C43") (pin "2") (pinfunction "2_2") (pintype "passive"))
      (node (ref "C44") (pin "2") (pinfunction "2_2") (pintype "passive"))
      (node (ref "C45") (pin "2") (pinfunction "2_2") (pintype "passive"))
      (node (ref "C46") (pin "2") (pinfunction "2_2") (pintype "passive"))
      (node (ref "C47") (pin "2") (pinfunction "2_2") (pintype "passive"))
      (node (ref "C48") (pin "2") (pinfunction "2_2") (pintype "passive"))
      (node (ref "C49") (pin "2") (pinfunction "2_2") (pintype "passive"))
      (node (ref "C50") (pin "2") (pinfunction "2_2") (pintype "passive"))
      (node (ref "C9") (pin "2") (pinfunction "2_2") (pintype "passive"))
      (node (ref "R26") (pin "2") (pinfunction "2_2") (pintype "passive"))
      (node (ref "R27") (pin "2") (pinfunction "2_2") (pintype "passive"))
      (node (ref "R28") (pin "2") (pinfunction "2_2") (pintype "passive"))
      (node (ref "R29") (pin "2") (pinfunction "2_2") (pintype "passive"))
      (node (ref "R31") (pin "2") (pinfunction "2_2") (pintype "passive"))
      (node (ref "R32") (pin "2") (pinfunction "2_2") (pintype "passive"))
      (node (ref "R34") (pin "2") (pinfunction "2_2") (pintype "passive"))
      (node (ref "U2") (pin "16") (pinfunction "GND_16") (pintype "power_in"))
      (node (ref "U2") (pin "17") (pinfunction "EP_17") (pintype "power_in"))
      (node (ref "U2") (pin "6") (pinfunction "VPRG2_6") (pintype "input"))
      (node (ref "U2") (pin "7") (pinfunction "VPRG1_7") (pintype "input"))
      (node (ref "U2") (pin "8") (pinfunction "GND_8") (pintype "power_in"))
      (node (ref "U3") (pin "3") (pinfunction "NC_3") (pintype "passive"))
      (node (ref "U3") (pin "4") (pinfunction "GND_4") (pintype "power_in"))
      (node (ref "U3") (pin "6") (pinfunction "NC_6") (pintype "passive"))
      (node (ref "U3") (pin "7") (pinfunction "NC_7") (pintype "passive"))
      (node (ref "U3") (pin "9") (pinfunction "EP_9") (pintype "power_in"))
      (node (ref "U4") (pin "2") (pinfunction "GND_2") (pintype "power_in"))
      (node (ref "U5") (pin "16") (pinfunction "GND_16") (pintype "power_in"))
      (node (ref "U5") (pin "17") (pinfunction "EP_17") (pintype "power_in"))
      (node (ref "U5") (pin "6") (pinfunction "VPRG2_6") (pintype "input"))
      (node (ref "U5") (pin "8") (pinfunction "GND_8") (pintype "power_in"))
      (node (ref "U6") (pin "3") (pinfunction "NC_3") (pintype "passive"))
      (node (ref "U6") (pin "4") (pinfunction "GND_4") (pintype "power_in"))
      (node (ref "U6") (pin "6") (pinfunction "NC_6") (pintype "passive"))
      (node (ref "U6") (pin "7") (pinfunction "NC_7") (pintype "passive"))
      (node (ref "U6") (pin "9") (pinfunction "EP_9") (pintype "power_in"))
      (node (ref "U7") (pin "2") (pinfunction "GND_2") (pintype "power_in"))
    )
    (net (code "2") (name "Net-(D1-A1)") (class "Default")
      (node (ref "C10") (pin "1") (pinfunction "1_1") (pintype "passive"))
      (node (ref "C9") (pin "1") (pinfunction "1_1") (pintype "passive"))
      (node (ref "D1") (pin "1") (pinfunction "A1_1") (pintype "passive"))
      (node (ref "L1") (pin "2") (pinfunction "2_2") (pintype "passive"))
    )
    (net (code "3") (name "Net-(D1-A2)") (class "Default")
      (node (ref "D1") (pin "2") (pinfunction "A2_2") (pintype "passive"))
      (node (ref "U3") (pin "1") (pinfunction "OUT_1") (pintype "power_in"))
    )
    (net (code "4") (name "Net-(D1-K)") (class "Default")
      (node (ref "C16") (pin "1") (pinfunction "1_1") (pintype "passive"))
      (node (ref "C18") (pin "1") (pinfunction "1_1") (pintype "passive"))
      (node (ref "C24") (pin "1") (pinfunction "1_1") (pintype "passive"))
      (node (ref "C25") (pin "1") (pinfunction "1_1") (pintype "passive"))
      (node (ref "C26") (pin "1") (pinfunction "1_1") (pintype "passive"))
      (node (ref "C27") (pin "1") (pinfunction "1_1") (pintype "passive"))
      (node (ref "D1") (pin "3") (pinfunction "K_3") (pintype "passive"))
      (node (ref "R24") (pin "1") (pinfunction "1_1") (pintype "passive"))
      (node (ref "R25") (pin "1") (pinfunction "1_1") (pintype "passive"))
      (node (ref "U4") (pin "1") (pinfunction "VIN_1") (pintype "power_in"))
      (node (ref "U4") (pin "3") (pinfunction "EN_3") (pintype "input"))
    )
    (net (code "5") (name "Net-(D2-A1)") (class "Default")
      (node (ref "C30") (pin "1") (pinfunction "1_1") (pintype "passive"))
      (node (ref "C31") (pin "1") (pinfunction "1_1") (pintype "passive"))
      (node (ref "D2") (pin "1") (pinfunction "A1_1") (pintype "passive"))
      (node (ref "L2") (pin "2") (pinfunction "2_2") (pintype "passive"))
    )
    (net (code "6") (name "Net-(D2-A2)") (class "Default")
      (node (ref "D2") (pin "2") (pinfunction "A2_2") (pintype "passive"))
      (node (ref "U6") (pin "1") (pinfunction "OUT_1") (pintype "power_in"))
    )
    (net (code "7") (name "Net-(D2-K)") (class "Default")
      (node (ref "C33") (pin "1") (pinfunction "1_1") (pintype "passive"))
      (node (ref "C39") (pin "1") (pinfunction "1_1") (pintype "passive"))
      (node (ref "C45") (pin "1") (pinfunction "1_1") (pintype "passive"))
      (node (ref "C46") (pin "1") (pinfunction "1_1") (pintype "passive"))
      (node (ref "C47") (pin "1") (pinfunction "1_1") (pintype "passive"))
      (node (ref "C48") (pin "1") (pinfunction "1_1") (pintype "passive"))
      (node (ref "D2") (pin "3") (pinfunction "K_3") (pintype "passive"))
      (node (ref "R33") (pin "1") (pinfunction "1_1") (pintype "passive"))
      (node (ref "U5") (pin "9") (pinfunction "VFB_9") (pintype "input"))
      (node (ref "U7") (pin "1") (pinfunction "VIN_1") (pintype "power_in"))
      (node (ref "U7") (pin "3") (pinfunction "EN_3") (pintype "input"))
    )
    (net (code "8") (name "Net-(U2-ISET)") (class "Default")
      (node (ref "R27") (pin "1") (pinfunction "1_1") (pintype "passive"))
      (node (ref "U2") (pin "11") (pinfunction "ISET_11") (pintype "input"))
    )
    (net (code "9") (name "Net-(U2-OVLO)") (class "Default")
      (node (ref "R23") (pin "2") (pinfunction "2_2") (pintype "passive"))
      (node (ref "R26") (pin "1") (pinfunction "1_1") (pintype "passive"))
      (node (ref "U2") (pin "12") (pinfunction "OVLO_12") (pintype "input"))
    )
    (net (code "10") (name "Net-(U2-SS)") (class "Default")
      (node (ref "C17") (pin "1") (pinfunction "1_1") (pintype "passive"))
      (node (ref "U2") (pin "10") (pinfunction "SS_10") (pintype "input"))
    )
    (net (code "11") (name "Net-(U2-SW)") (class "Default")
      (node (ref "L1") (pin "1") (pinfunction "1_1") (pintype "passive"))
      (node (ref "U2") (pin "1") (pinfunction "SW_1") (pintype "power_in"))
    )
    (net (code "12") (name "Net-(U2-VFB)") (class "Default")
      (node (ref "R24") (pin "2") (pinfunction "2_2") (pintype "passive"))
      (node (ref "R28") (pin "1") (pinfunction "1_1") (pintype "passive"))
      (node (ref "U2") (pin "9") (pinfunction "VFB_9") (pintype "input"))
    )
    (net (code "13") (name "Net-(U2-VIN)") (class "Default")
      (node (ref "C19") (pin "1") (pinfunction "1_1") (pintype "passive"))
      (node (ref "C20") (pin "1") (pinfunction "1_1") (pintype "passive"))
      (node (ref "C21") (pin "1") (pinfunction "1_1") (pintype "passive"))
      (node (ref "C22") (pin "1") (pinfunction "1_1") (pintype "passive"))
      (node (ref "C23") (pin "1") (pinfunction "1_1") (pintype "passive"))
      (node (ref "R23") (pin "1") (pinfunction "1_1") (pintype "passive"))
      (node (ref "U2") (pin "3") (pinfunction "VIN_3") (pintype "power_in"))
    )
    (net (code "14") (name "Net-(U3-FB)") (class "Default")
      (node (ref "C16") (pin "2") (pinfunction "2_2") (pintype "passive"))
      (node (ref "R25") (pin "2") (pinfunction "2_2") (pintype "passive"))
      (node (ref "R29") (pin "1") (pinfunction "1_1") (pintype "passive"))
      (node (ref "U3") (pin "2") (pinfunction "FB_2") (pintype "input"))
    )
    (net (code "15") (name "Net-(U3-IN)") (class "Default")
      (node (ref "C11") (pin "1") (pinfunction "1_1") (pintype "passive"))
      (node (ref "C12") (pin "1") (pinfunction "1_1") (pintype "passive"))
      (node (ref "C13") (pin "1") (pinfunction "1_1") (pintype "passive"))
      (node (ref "C14") (pin "1") (pinfunction "1_1") (pintype "passive"))
      (node (ref "C15") (pin "1") (pinfunction "1_1") (pintype "passive"))
      (node (ref "U3") (pin "8") (pinfunction "IN_8") (pintype "power_in"))
    )
    (net (code "16") (name "Net-(U4-BYP)") (class "Default")
      (node (ref "C28") (pin "1") (pinfunction "1_1") (pintype "passive"))
      (node (ref "U4") (pin "4") (pinfunction "BYP_4") (pintype "passive"))
    )
    (net (code "17") (name "Net-(U4-VOUT)") (class "Default")
      (node (ref "C29") (pin "1") (pinfunction "1_1") (pintype "passive"))
      (node (ref "U4") (pin "5") (pinfunction "VOUT_5") (pintype "power_in"))
    )
    (net (code "18") (name "Net-(U5-ISET)") (class "Default")
      (node (ref "R32") (pin "1") (pinfunction "1_1") (pintype "passive"))
      (node (ref "U5") (pin "11") (pinfunction "ISET_11") (pintype "input"))
    )
    (net (code "19") (name "Net-(U5-OVLO)") (class "Default")
      (node (ref "R30") (pin "2") (pinfunction "2_2") (pintype "passive"))
      (node (ref "R31") (pin "1") (pinfunction "1_1") (pintype "passive"))
      (node (ref "U5") (pin "12") (pinfunction "OVLO_12") (pintype "input"))
    )
    (net (code "20") (name "Net-(U5-SS)") (class "Default")
      (node (ref "C32") (pin "1") (pinfunction "1_1") (pintype "passive"))
      (node (ref "U5") (pin "10") (pinfunction "SS_10") (pintype "input"))
      (node (ref "U5") (pin "7") (pinfunction "VPRG1_7") (pintype "input"))
    )
    (net (code "21") (name "Net-(U5-SW)") (class "Default")
      (node (ref "L2") (pin "1") (pinfunction "1_1") (pintype "passive"))
      (node (ref "U5") (pin "1") (pinfunction "SW_1") (pintype "power_in"))
    )
    (net (code "22") (name "Net-(U5-VIN)") (class "Default")
      (node (ref "C40") (pin "1") (pinfunction "1_1") (pintype "passive"))
      (node (ref "C41") (pin "1") (pinfunction "1_1") (pintype "passive"))
      (node (ref "C42") (pin "1") (pinfunction "1_1") (pintype "passive"))
      (node (ref "C43") (pin "1") (pinfunction "1_1") (pintype "passive"))
      (node (ref "C44") (pin "1") (pinfunction "1_1") (pintype "passive"))
      (node (ref "R30") (pin "1") (pinfunction "1_1") (pintype "passive"))
      (node (ref "U5") (pin "3") (pinfunction "VIN_3") (pintype "power_in"))
    )
    (net (code "23") (name "Net-(U6-FB)") (class "Default")
      (node (ref "C39") (pin "2") (pinfunction "2_2") (pintype "passive"))
      (node (ref "R33") (pin "2") (pinfunction "2_2") (pintype "passive"))
      (node (ref "R34") (pin "1") (pinfunction "1_1") (pintype "passive"))
      (node (ref "U6") (pin "2") (pinfunction "FB_2") (pintype "input"))
    )
    (net (code "24") (name "Net-(U6-IN)") (class "Default")
      (node (ref "C34") (pin "1") (pinfunction "1_1") (pintype "passive"))
      (node (ref "C35") (pin "1") (pinfunction "1_1") (pintype "passive"))
      (node (ref "C36") (pin "1") (pinfunction "1_1") (pintype "passive"))
      (node (ref "C37") (pin "1") (pinfunction "1_1") (pintype "passive"))
      (node (ref "C38") (pin "1") (pinfunction "1_1") (pintype "passive"))
      (node (ref "U6") (pin "8") (pinfunction "IN_8") (pintype "power_in"))
    )
    (net (code "25") (name "Net-(U7-BYP)") (class "Default")
      (node (ref "C49") (pin "1") (pinfunction "1_1") (pintype "passive"))
      (node (ref "U7") (pin "4") (pinfunction "BYP_4") (pintype "passive"))
    )
    (net (code "26") (name "Net-(U7-VOUT)") (class "Default")
      (node (ref "C50") (pin "1") (pinfunction "1_1") (pintype "passive"))
      (node (ref "U7") (pin "5") (pinfunction "VOUT_5") (pintype "power_in"))
    )
    (net (code "27") (name "unconnected-(U2-FBO-Pad5)") (class "Default")
      (node (ref "U2") (pin "5") (pinfunction "FBO_5") (pintype "output+no_connect"))
    )
    (net (code "28") (name "unconnected-(U2-RUN-Pad14)") (class "Default")
      (node (ref "U2") (pin "14") (pinfunction "RUN_14") (pintype "input"))
    )
    (net (code "29") (name "unconnected-(U3-EN-Pad5)") (class "Default")
      (node (ref "U3") (pin "5") (pinfunction "EN_5") (pintype "input"))
    )
    (net (code "30") (name "unconnected-(U5-FBO-Pad5)") (class "Default")
      (node (ref "U5") (pin "5") (pinfunction "FBO_5") (pintype "output+no_connect"))
    )
    (net (code "31") (name "unconnected-(U5-RUN-Pad14)") (class "Default")
      (node (ref "U5") (pin "14") (pinfunction "RUN_14") (pintype "input"))
    )
    (net (code "32") (name "unconnected-(U6-EN-Pad5)") (class "Default")
      (node (ref "U6") (pin "5") (pinfunction "EN_5") (pintype "input"))
    )
  )
)
